# step1710051029.net
KiCad netlist of a schematic drawn in Altium Designer
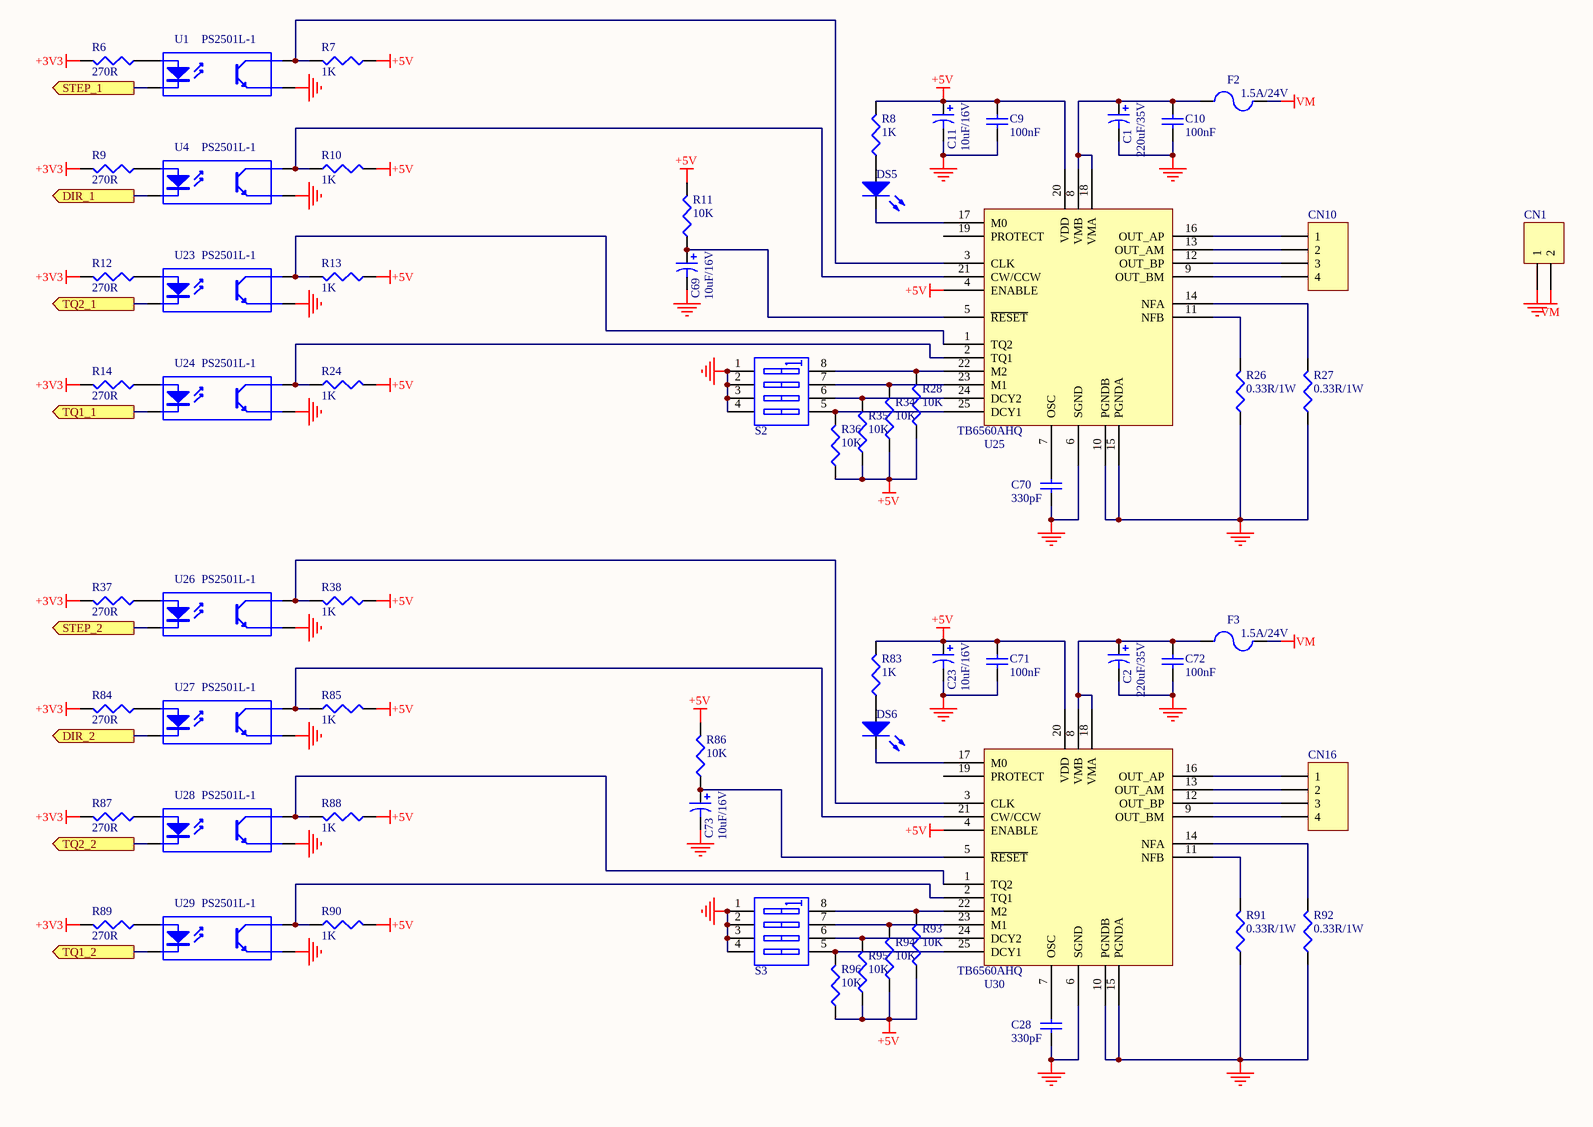
[diagram p0: step1710051029.SchDoc]

(export (version "E")
  (design (tool "Eeschema 10.0.6"))
  (components
    (comp (ref "C1")
      (value "220uF/35V")
      (footprint "CAP-D10/L13")
      (description "Polarized Capacitor (Radial)")
      (fields (field (name "PUBLISHER") "Altium Limited"))
      (libsource (lib "Miscellaneous Devices") (part "Cap Pol1"))
    )
    (comp (ref "C2")
      (value "220uF/35V")
      (footprint "CAP-D10/L13")
      (description "Polarized Capacitor (Radial)")
      (fields (field (name "PUBLISHER") "Altium Limited"))
      (libsource (lib "Miscellaneous Devices") (part "Cap Pol1"))
    )
    (comp (ref "C9")
      (value "100nF")
      (footprint "C0603-3")
      (description "Capacitor")
      (fields (field (name "PUBLISHER") "Altium Limited"))
      (libsource (lib "Miscellaneous Devices") (part "Cap"))
    )
    (comp (ref "C10")
      (value "100nF")
      (footprint "C0603-3")
      (description "Capacitor")
      (fields (field (name "PUBLISHER") "Altium Limited"))
      (libsource (lib "Miscellaneous Devices") (part "Cap"))
    )
    (comp (ref "C11")
      (value "10uF/16V")
      (footprint "CE1210")
      (description "Polarized Capacitor (Radial)")
      (fields (field (name "PUBLISHER") "Altium Limited"))
      (libsource (lib "Miscellaneous Devices") (part "Cap Pol1"))
    )
    (comp (ref "C23")
      (value "10uF/16V")
      (footprint "CE1210")
      (description "Polarized Capacitor (Radial)")
      (fields (field (name "PUBLISHER") "Altium Limited"))
      (libsource (lib "Miscellaneous Devices") (part "Cap Pol1"))
    )
    (comp (ref "C28")
      (value "330pF")
      (footprint "C0603-3")
      (description "Capacitor")
      (fields (field (name "PUBLISHER") "Altium Limited"))
      (libsource (lib "Miscellaneous Devices") (part "Cap"))
    )
    (comp (ref "C69")
      (value "10uF/16V")
      (footprint "CE1210")
      (description "Polarized Capacitor (Radial)")
      (fields (field (name "PUBLISHER") "Altium Limited"))
      (libsource (lib "Miscellaneous Devices") (part "Cap Pol1"))
    )
    (comp (ref "C70")
      (value "330pF")
      (footprint "C0603-3")
      (description "Capacitor")
      (fields (field (name "PUBLISHER") "Altium Limited"))
      (libsource (lib "Miscellaneous Devices") (part "Cap"))
    )
    (comp (ref "C71")
      (value "100nF")
      (footprint "C0603-3")
      (description "Capacitor")
      (fields (field (name "PUBLISHER") "Altium Limited"))
      (libsource (lib "Miscellaneous Devices") (part "Cap"))
    )
    (comp (ref "C72")
      (value "100nF")
      (footprint "C0603-3")
      (description "Capacitor")
      (fields (field (name "PUBLISHER") "Altium Limited"))
      (libsource (lib "Miscellaneous Devices") (part "Cap"))
    )
    (comp (ref "C73")
      (value "10uF/16V")
      (footprint "CE1210")
      (description "Polarized Capacitor (Radial)")
      (fields (field (name "PUBLISHER") "Altium Limited"))
      (libsource (lib "Miscellaneous Devices") (part "Cap Pol1"))
    )
    (comp (ref "CN1")
      (value "~")
      (footprint "XHS2-2.5")
      (description "Header, 2-Pin")
      (fields (field (name "PUBLISHER") "Altium Limited"))
      (libsource (lib "Miscellaneous Connectors") (part "Header 2"))
    )
    (comp (ref "CN10")
      (value "~")
      (footprint "XHS4-2.5")
      (description "Header, 4-Pin")
      (fields (field (name "PUBLISHER") "Altium Limited"))
      (libsource (lib "Miscellaneous Connectors") (part "Header 4"))
    )
    (comp (ref "CN16")
      (value "~")
      (footprint "XHS4-2.5")
      (description "Header, 4-Pin")
      (fields (field (name "PUBLISHER") "Altium Limited"))
      (libsource (lib "Miscellaneous Connectors") (part "Header 4"))
    )
    (comp (ref "DS5")
      (value "~")
      (footprint "LED-0805")
      (description "Typical INFRARED GaAs LED")
      (fields (field (name "PUBLISHER") "Altium Limited"))
      (libsource (lib "Sch1609122025") (part "LED0"))
    )
    (comp (ref "DS6")
      (value "~")
      (footprint "LED-0805")
      (description "Typical INFRARED GaAs LED")
      (fields (field (name "PUBLISHER") "Altium Limited"))
      (libsource (lib "Sch1609122025") (part "LED0"))
    )
    (comp (ref "F2")
      (value "1.5A/24V")
      (footprint "1812")
      (libsource (lib "SchLib1512020919") (part "Fuse 2"))
    )
    (comp (ref "F3")
      (value "1.5A/24V")
      (footprint "1812")
      (libsource (lib "SchLib1512020919") (part "Fuse 2"))
    )
    (comp (ref "R6")
      (value "270R")
      (footprint "R0603-3")
      (description "Resistor")
      (fields (field (name "PUBLISHER") "Altium Limited"))
      (libsource (lib "Miscellaneous Devices") (part "Res3"))
    )
    (comp (ref "R7")
      (value "1K")
      (footprint "R0603-3")
      (description "Resistor")
      (fields (field (name "PUBLISHER") "Altium Limited"))
      (libsource (lib "Miscellaneous Devices") (part "Res3"))
    )
    (comp (ref "R8")
      (value "1K")
      (footprint "R0603-3")
      (description "Resistor")
      (fields (field (name "PUBLISHER") "Altium Limited"))
      (libsource (lib "Miscellaneous Devices") (part "Res3"))
    )
    (comp (ref "R9")
      (value "270R")
      (footprint "R0603-3")
      (description "Resistor")
      (fields (field (name "PUBLISHER") "Altium Limited"))
      (libsource (lib "Miscellaneous Devices") (part "Res3"))
    )
    (comp (ref "R10")
      (value "1K")
      (footprint "R0603-3")
      (description "Resistor")
      (fields (field (name "PUBLISHER") "Altium Limited"))
      (libsource (lib "Miscellaneous Devices") (part "Res3"))
    )
    (comp (ref "R11")
      (value "10K")
      (footprint "R0603-3")
      (description "Resistor")
      (fields (field (name "PUBLISHER") "Altium Limited"))
      (libsource (lib "Miscellaneous Devices") (part "Res3"))
    )
    (comp (ref "R12")
      (value "270R")
      (footprint "R0603-3")
      (description "Resistor")
      (fields (field (name "PUBLISHER") "Altium Limited"))
      (libsource (lib "Miscellaneous Devices") (part "Res3"))
    )
    (comp (ref "R13")
      (value "1K")
      (footprint "R0603-3")
      (description "Resistor")
      (fields (field (name "PUBLISHER") "Altium Limited"))
      (libsource (lib "Miscellaneous Devices") (part "Res3"))
    )
    (comp (ref "R14")
      (value "270R")
      (footprint "R0603-3")
      (description "Resistor")
      (fields (field (name "PUBLISHER") "Altium Limited"))
      (libsource (lib "Miscellaneous Devices") (part "Res3"))
    )
    (comp (ref "R24")
      (value "1K")
      (footprint "R0603-3")
      (description "Resistor")
      (fields (field (name "PUBLISHER") "Altium Limited"))
      (libsource (lib "Miscellaneous Devices") (part "Res3"))
    )
    (comp (ref "R26")
      (value "0.33R/1W")
      (footprint "2512")
      (description "Resistor")
      (fields (field (name "PUBLISHER") "Altium Limited"))
      (libsource (lib "Miscellaneous Devices") (part "Res3"))
    )
    (comp (ref "R27")
      (value "0.33R/1W")
      (footprint "2512")
      (description "Resistor")
      (fields (field (name "PUBLISHER") "Altium Limited"))
      (libsource (lib "Miscellaneous Devices") (part "Res3"))
    )
    (comp (ref "R28")
      (value "10K")
      (footprint "R0603-3")
      (description "Resistor")
      (fields (field (name "PUBLISHER") "Altium Limited"))
      (libsource (lib "Miscellaneous Devices") (part "Res3"))
    )
    (comp (ref "R34")
      (value "10K")
      (footprint "R0603-3")
      (description "Resistor")
      (fields (field (name "PUBLISHER") "Altium Limited"))
      (libsource (lib "Miscellaneous Devices") (part "Res3"))
    )
    (comp (ref "R35")
      (value "10K")
      (footprint "R0603-3")
      (description "Resistor")
      (fields (field (name "PUBLISHER") "Altium Limited"))
      (libsource (lib "Miscellaneous Devices") (part "Res3"))
    )
    (comp (ref "R36")
      (value "10K")
      (footprint "R0603-3")
      (description "Resistor")
      (fields (field (name "PUBLISHER") "Altium Limited"))
      (libsource (lib "Miscellaneous Devices") (part "Res3"))
    )
    (comp (ref "R37")
      (value "270R")
      (footprint "R0603-3")
      (description "Resistor")
      (fields (field (name "PUBLISHER") "Altium Limited"))
      (libsource (lib "Miscellaneous Devices") (part "Res3"))
    )
    (comp (ref "R38")
      (value "1K")
      (footprint "R0603-3")
      (description "Resistor")
      (fields (field (name "PUBLISHER") "Altium Limited"))
      (libsource (lib "Miscellaneous Devices") (part "Res3"))
    )
    (comp (ref "R83")
      (value "1K")
      (footprint "R0603-3")
      (description "Resistor")
      (fields (field (name "PUBLISHER") "Altium Limited"))
      (libsource (lib "Miscellaneous Devices") (part "Res3"))
    )
    (comp (ref "R84")
      (value "270R")
      (footprint "R0603-3")
      (description "Resistor")
      (fields (field (name "PUBLISHER") "Altium Limited"))
      (libsource (lib "Miscellaneous Devices") (part "Res3"))
    )
    (comp (ref "R85")
      (value "1K")
      (footprint "R0603-3")
      (description "Resistor")
      (fields (field (name "PUBLISHER") "Altium Limited"))
      (libsource (lib "Miscellaneous Devices") (part "Res3"))
    )
    (comp (ref "R86")
      (value "10K")
      (footprint "R0603-3")
      (description "Resistor")
      (fields (field (name "PUBLISHER") "Altium Limited"))
      (libsource (lib "Miscellaneous Devices") (part "Res3"))
    )
    (comp (ref "R87")
      (value "270R")
      (footprint "R0603-3")
      (description "Resistor")
      (fields (field (name "PUBLISHER") "Altium Limited"))
      (libsource (lib "Miscellaneous Devices") (part "Res3"))
    )
    (comp (ref "R88")
      (value "1K")
      (footprint "R0603-3")
      (description "Resistor")
      (fields (field (name "PUBLISHER") "Altium Limited"))
      (libsource (lib "Miscellaneous Devices") (part "Res3"))
    )
    (comp (ref "R89")
      (value "270R")
      (footprint "R0603-3")
      (description "Resistor")
      (fields (field (name "PUBLISHER") "Altium Limited"))
      (libsource (lib "Miscellaneous Devices") (part "Res3"))
    )
    (comp (ref "R90")
      (value "1K")
      (footprint "R0603-3")
      (description "Resistor")
      (fields (field (name "PUBLISHER") "Altium Limited"))
      (libsource (lib "Miscellaneous Devices") (part "Res3"))
    )
    (comp (ref "R91")
      (value "0.33R/1W")
      (footprint "2512")
      (description "Resistor")
      (fields (field (name "PUBLISHER") "Altium Limited"))
      (libsource (lib "Miscellaneous Devices") (part "Res3"))
    )
    (comp (ref "R92")
      (value "0.33R/1W")
      (footprint "2512")
      (description "Resistor")
      (fields (field (name "PUBLISHER") "Altium Limited"))
      (libsource (lib "Miscellaneous Devices") (part "Res3"))
    )
    (comp (ref "R93")
      (value "10K")
      (footprint "R0603-3")
      (description "Resistor")
      (fields (field (name "PUBLISHER") "Altium Limited"))
      (libsource (lib "Miscellaneous Devices") (part "Res3"))
    )
    (comp (ref "R94")
      (value "10K")
      (footprint "R0603-3")
      (description "Resistor")
      (fields (field (name "PUBLISHER") "Altium Limited"))
      (libsource (lib "Miscellaneous Devices") (part "Res3"))
    )
    (comp (ref "R95")
      (value "10K")
      (footprint "R0603-3")
      (description "Resistor")
      (fields (field (name "PUBLISHER") "Altium Limited"))
      (libsource (lib "Miscellaneous Devices") (part "Res3"))
    )
    (comp (ref "R96")
      (value "10K")
      (footprint "R0603-3")
      (description "Resistor")
      (fields (field (name "PUBLISHER") "Altium Limited"))
      (libsource (lib "Miscellaneous Devices") (part "Res3"))
    )
    (comp (ref "S2")
      (value "~")
      (footprint "SDSW8-H")
      (description "DIP Switch, 4 Position, SPST")
      (fields (field (name "PUBLISHER") "Altium Limited"))
      (libsource (lib "Miscellaneous Devices") (part "SW DIP-4"))
    )
    (comp (ref "S3")
      (value "~")
      (footprint "SDSW8-H")
      (description "DIP Switch, 4 Position, SPST")
      (fields (field (name "PUBLISHER") "Altium Limited"))
      (libsource (lib "Miscellaneous Devices") (part "SW DIP-4"))
    )
    (comp (ref "U1")
      (value "PS2501L-1")
      (footprint "SOP4-2.54")
      (libsource (lib "GprsCanSchLib") (part "PC187"))
    )
    (comp (ref "U4")
      (value "PS2501L-1")
      (footprint "SOP4-2.54")
      (libsource (lib "GprsCanSchLib") (part "PC187"))
    )
    (comp (ref "U23")
      (value "PS2501L-1")
      (footprint "SOP4-2.54")
      (libsource (lib "GprsCanSchLib") (part "PC187"))
    )
    (comp (ref "U24")
      (value "PS2501L-1")
      (footprint "SOP4-2.54")
      (libsource (lib "GprsCanSchLib") (part "PC187"))
    )
    (comp (ref "U25")
      (value "TB6560AHQ")
      (footprint "HZIP25-P-1.27")
      (description "PWM Chopper-Type Bipolar Driver IC for Stepping Motor Control")
      (libsource (lib "Sch1705290855") (part "TB6560AHQ"))
    )
    (comp (ref "U26")
      (value "PS2501L-1")
      (footprint "SOP4-2.54")
      (libsource (lib "GprsCanSchLib") (part "PC187"))
    )
    (comp (ref "U27")
      (value "PS2501L-1")
      (footprint "SOP4-2.54")
      (libsource (lib "GprsCanSchLib") (part "PC187"))
    )
    (comp (ref "U28")
      (value "PS2501L-1")
      (footprint "SOP4-2.54")
      (libsource (lib "GprsCanSchLib") (part "PC187"))
    )
    (comp (ref "U29")
      (value "PS2501L-1")
      (footprint "SOP4-2.54")
      (libsource (lib "GprsCanSchLib") (part "PC187"))
    )
    (comp (ref "U30")
      (value "TB6560AHQ")
      (footprint "HZIP25-P-1.27")
      (description "PWM Chopper-Type Bipolar Driver IC for Stepping Motor Control")
      (libsource (lib "Sch1705290855") (part "TB6560AHQ"))
    )
  )
  (nets
    (net (code "1") (name "+3V3") (class "Default")
      (node (ref "R12") (pin "2") (pinfunction "2_2") (pintype "passive"))
      (node (ref "R14") (pin "2") (pinfunction "2_2") (pintype "passive"))
      (node (ref "R37") (pin "2") (pinfunction "2_2") (pintype "passive"))
      (node (ref "R6") (pin "2") (pinfunction "2_2") (pintype "passive"))
      (node (ref "R84") (pin "2") (pinfunction "2_2") (pintype "passive"))
      (node (ref "R87") (pin "2") (pinfunction "2_2") (pintype "passive"))
      (node (ref "R89") (pin "2") (pinfunction "2_2") (pintype "passive"))
      (node (ref "R9") (pin "2") (pinfunction "2_2") (pintype "passive"))
    )
    (net (code "2") (name "+5V") (class "Default")
      (node (ref "C11") (pin "1") (pinfunction "1_1") (pintype "passive"))
      (node (ref "C23") (pin "1") (pinfunction "1_1") (pintype "passive"))
      (node (ref "C71") (pin "1") (pinfunction "1_1") (pintype "passive"))
      (node (ref "C9") (pin "1") (pinfunction "1_1") (pintype "passive"))
      (node (ref "R10") (pin "2") (pinfunction "2_2") (pintype "passive"))
      (node (ref "R11") (pin "2") (pinfunction "2_2") (pintype "passive"))
      (node (ref "R13") (pin "1") (pinfunction "1_1") (pintype "passive"))
      (node (ref "R24") (pin "2") (pinfunction "2_2") (pintype "passive"))
      (node (ref "R28") (pin "1") (pinfunction "1_1") (pintype "passive"))
      (node (ref "R34") (pin "1") (pinfunction "1_1") (pintype "passive"))
      (node (ref "R35") (pin "1") (pinfunction "1_1") (pintype "passive"))
      (node (ref "R36") (pin "1") (pinfunction "1_1") (pintype "passive"))
      (node (ref "R38") (pin "1") (pinfunction "1_1") (pintype "passive"))
      (node (ref "R7") (pin "1") (pinfunction "1_1") (pintype "passive"))
      (node (ref "R8") (pin "2") (pinfunction "2_2") (pintype "passive"))
      (node (ref "R83") (pin "2") (pinfunction "2_2") (pintype "passive"))
      (node (ref "R85") (pin "2") (pinfunction "2_2") (pintype "passive"))
      (node (ref "R86") (pin "2") (pinfunction "2_2") (pintype "passive"))
      (node (ref "R88") (pin "1") (pinfunction "1_1") (pintype "passive"))
      (node (ref "R90") (pin "2") (pinfunction "2_2") (pintype "passive"))
      (node (ref "R93") (pin "1") (pinfunction "1_1") (pintype "passive"))
      (node (ref "R94") (pin "1") (pinfunction "1_1") (pintype "passive"))
      (node (ref "R95") (pin "1") (pinfunction "1_1") (pintype "passive"))
      (node (ref "R96") (pin "1") (pinfunction "1_1") (pintype "passive"))
      (node (ref "U25") (pin "20") (pinfunction "VDD_20") (pintype "passive"))
      (node (ref "U25") (pin "4") (pinfunction "ENABLE_4") (pintype "passive"))
      (node (ref "U30") (pin "20") (pinfunction "VDD_20") (pintype "passive"))
      (node (ref "U30") (pin "4") (pinfunction "ENABLE_4") (pintype "passive"))
    )
    (net (code "3") (name "/DIR_1") (class "Default")
      (node (ref "U4") (pin "2") (pinfunction "K_2") (pintype "passive"))
    )
    (net (code "4") (name "/DIR_2") (class "Default")
      (node (ref "U27") (pin "2") (pinfunction "K_2") (pintype "passive"))
    )
    (net (code "5") (name "/STEP_1") (class "Default")
      (node (ref "U1") (pin "2") (pinfunction "K_2") (pintype "passive"))
    )
    (net (code "6") (name "/STEP_2") (class "Default")
      (node (ref "U26") (pin "2") (pinfunction "K_2") (pintype "passive"))
    )
    (net (code "7") (name "/TQ1_1") (class "Default")
      (node (ref "U24") (pin "2") (pinfunction "K_2") (pintype "passive"))
    )
    (net (code "8") (name "/TQ1_2") (class "Default")
      (node (ref "U29") (pin "2") (pinfunction "K_2") (pintype "passive"))
    )
    (net (code "9") (name "/TQ2_1") (class "Default")
      (node (ref "U23") (pin "2") (pinfunction "K_2") (pintype "passive"))
    )
    (net (code "10") (name "/TQ2_2") (class "Default")
      (node (ref "U28") (pin "2") (pinfunction "K_2") (pintype "passive"))
    )
    (net (code "11") (name "GND") (class "Default")
      (node (ref "C1") (pin "2") (pinfunction "2_2") (pintype "passive"))
      (node (ref "C10") (pin "2") (pinfunction "2_2") (pintype "passive"))
      (node (ref "C11") (pin "2") (pinfunction "2_2") (pintype "passive"))
      (node (ref "C2") (pin "2") (pinfunction "2_2") (pintype "passive"))
      (node (ref "C23") (pin "2") (pinfunction "2_2") (pintype "passive"))
      (node (ref "C28") (pin "2") (pinfunction "2_2") (pintype "passive"))
      (node (ref "C69") (pin "2") (pinfunction "2_2") (pintype "passive"))
      (node (ref "C70") (pin "2") (pinfunction "2_2") (pintype "passive"))
      (node (ref "C71") (pin "2") (pinfunction "2_2") (pintype "passive"))
      (node (ref "C72") (pin "2") (pinfunction "2_2") (pintype "passive"))
      (node (ref "C73") (pin "2") (pinfunction "2_2") (pintype "passive"))
      (node (ref "C9") (pin "2") (pinfunction "2_2") (pintype "passive"))
      (node (ref "CN1") (pin "1") (pinfunction "1_1") (pintype "passive"))
      (node (ref "R26") (pin "1") (pinfunction "1_1") (pintype "passive"))
      (node (ref "R27") (pin "1") (pinfunction "1_1") (pintype "passive"))
      (node (ref "R91") (pin "1") (pinfunction "1_1") (pintype "passive"))
      (node (ref "R92") (pin "1") (pinfunction "1_1") (pintype "passive"))
      (node (ref "S2") (pin "1") (pinfunction "A1_1") (pintype "passive"))
      (node (ref "S2") (pin "2") (pinfunction "A2_2") (pintype "passive"))
      (node (ref "S2") (pin "3") (pinfunction "A3_3") (pintype "passive"))
      (node (ref "S2") (pin "4") (pinfunction "A4_4") (pintype "passive"))
      (node (ref "S3") (pin "1") (pinfunction "A1_1") (pintype "passive"))
      (node (ref "S3") (pin "2") (pinfunction "A2_2") (pintype "passive"))
      (node (ref "S3") (pin "3") (pinfunction "A3_3") (pintype "passive"))
      (node (ref "S3") (pin "4") (pinfunction "A4_4") (pintype "passive"))
      (node (ref "U1") (pin "3") (pinfunction "C_3") (pintype "passive"))
      (node (ref "U23") (pin "3") (pinfunction "C_3") (pintype "passive"))
      (node (ref "U24") (pin "3") (pinfunction "C_3") (pintype "passive"))
      (node (ref "U25") (pin "10") (pinfunction "PGNDB_10") (pintype "passive"))
      (node (ref "U25") (pin "15") (pinfunction "PGNDA_15") (pintype "passive"))
      (node (ref "U25") (pin "6") (pinfunction "SGND_6") (pintype "passive"))
      (node (ref "U26") (pin "3") (pinfunction "C_3") (pintype "passive"))
      (node (ref "U27") (pin "3") (pinfunction "C_3") (pintype "passive"))
      (node (ref "U28") (pin "3") (pinfunction "C_3") (pintype "passive"))
      (node (ref "U29") (pin "3") (pinfunction "C_3") (pintype "passive"))
      (node (ref "U30") (pin "10") (pinfunction "PGNDB_10") (pintype "passive"))
      (node (ref "U30") (pin "15") (pinfunction "PGNDA_15") (pintype "passive"))
      (node (ref "U30") (pin "6") (pinfunction "SGND_6") (pintype "passive"))
      (node (ref "U4") (pin "3") (pinfunction "C_3") (pintype "passive"))
    )
    (net (code "12") (name "Net-(DS5-A)") (class "Default")
      (node (ref "DS5") (pin "1") (pinfunction "A_1") (pintype "passive"))
      (node (ref "R8") (pin "1") (pinfunction "1_1") (pintype "passive"))
    )
    (net (code "13") (name "Net-(DS5-K)") (class "Default")
      (node (ref "DS5") (pin "2") (pinfunction "K_2") (pintype "passive"))
      (node (ref "U25") (pin "17") (pinfunction "M0_17") (pintype "passive"))
    )
    (net (code "14") (name "Net-(DS6-A)") (class "Default")
      (node (ref "DS6") (pin "1") (pinfunction "A_1") (pintype "passive"))
      (node (ref "R83") (pin "1") (pinfunction "1_1") (pintype "passive"))
    )
    (net (code "15") (name "Net-(DS6-K)") (class "Default")
      (node (ref "DS6") (pin "2") (pinfunction "K_2") (pintype "passive"))
      (node (ref "U30") (pin "17") (pinfunction "M0_17") (pintype "passive"))
    )
    (net (code "16") (name "Net-(S2-B1)") (class "Default")
      (node (ref "R28") (pin "2") (pinfunction "2_2") (pintype "passive"))
      (node (ref "S2") (pin "8") (pinfunction "B1_8") (pintype "passive"))
      (node (ref "U25") (pin "22") (pinfunction "M2_22") (pintype "passive"))
    )
    (net (code "17") (name "Net-(S2-B2)") (class "Default")
      (node (ref "R34") (pin "2") (pinfunction "2_2") (pintype "passive"))
      (node (ref "S2") (pin "7") (pinfunction "B2_7") (pintype "passive"))
      (node (ref "U25") (pin "23") (pinfunction "M1_23") (pintype "passive"))
    )
    (net (code "18") (name "Net-(S2-B3)") (class "Default")
      (node (ref "R35") (pin "2") (pinfunction "2_2") (pintype "passive"))
      (node (ref "S2") (pin "6") (pinfunction "B3_6") (pintype "passive"))
      (node (ref "U25") (pin "24") (pinfunction "DCY2_24") (pintype "passive"))
    )
    (net (code "19") (name "Net-(S2-B4)") (class "Default")
      (node (ref "R36") (pin "2") (pinfunction "2_2") (pintype "passive"))
      (node (ref "S2") (pin "5") (pinfunction "B4_5") (pintype "passive"))
      (node (ref "U25") (pin "25") (pinfunction "DCY1_25") (pintype "passive"))
    )
    (net (code "20") (name "Net-(S3-B1)") (class "Default")
      (node (ref "R93") (pin "2") (pinfunction "2_2") (pintype "passive"))
      (node (ref "S3") (pin "8") (pinfunction "B1_8") (pintype "passive"))
      (node (ref "U30") (pin "22") (pinfunction "M2_22") (pintype "passive"))
    )
    (net (code "21") (name "Net-(S3-B2)") (class "Default")
      (node (ref "R94") (pin "2") (pinfunction "2_2") (pintype "passive"))
      (node (ref "S3") (pin "7") (pinfunction "B2_7") (pintype "passive"))
      (node (ref "U30") (pin "23") (pinfunction "M1_23") (pintype "passive"))
    )
    (net (code "22") (name "Net-(S3-B3)") (class "Default")
      (node (ref "R95") (pin "2") (pinfunction "2_2") (pintype "passive"))
      (node (ref "S3") (pin "6") (pinfunction "B3_6") (pintype "passive"))
      (node (ref "U30") (pin "24") (pinfunction "DCY2_24") (pintype "passive"))
    )
    (net (code "23") (name "Net-(S3-B4)") (class "Default")
      (node (ref "R96") (pin "2") (pinfunction "2_2") (pintype "passive"))
      (node (ref "S3") (pin "5") (pinfunction "B4_5") (pintype "passive"))
      (node (ref "U30") (pin "25") (pinfunction "DCY1_25") (pintype "passive"))
    )
    (net (code "24") (name "Net-(U1-A)") (class "Default")
      (node (ref "R6") (pin "1") (pinfunction "1_1") (pintype "passive"))
      (node (ref "U1") (pin "1") (pinfunction "A_1") (pintype "passive"))
    )
    (net (code "25") (name "Net-(U1-D)") (class "Default")
      (node (ref "R7") (pin "2") (pinfunction "2_2") (pintype "passive"))
      (node (ref "U1") (pin "4") (pinfunction "D_4") (pintype "passive"))
      (node (ref "U25") (pin "3") (pinfunction "CLK_3") (pintype "passive"))
    )
    (net (code "26") (name "Net-(U4-A)") (class "Default")
      (node (ref "R9") (pin "1") (pinfunction "1_1") (pintype "passive"))
      (node (ref "U4") (pin "1") (pinfunction "A_1") (pintype "passive"))
    )
    (net (code "27") (name "Net-(U23-A)") (class "Default")
      (node (ref "R12") (pin "1") (pinfunction "1_1") (pintype "passive"))
      (node (ref "U23") (pin "1") (pinfunction "A_1") (pintype "passive"))
    )
    (net (code "28") (name "Net-(U23-D)") (class "Default")
      (node (ref "R13") (pin "2") (pinfunction "2_2") (pintype "passive"))
      (node (ref "U23") (pin "4") (pinfunction "D_4") (pintype "passive"))
      (node (ref "U25") (pin "1") (pinfunction "TQ2_1") (pintype "passive"))
    )
    (net (code "29") (name "Net-(U24-A)") (class "Default")
      (node (ref "R14") (pin "1") (pinfunction "1_1") (pintype "passive"))
      (node (ref "U24") (pin "1") (pinfunction "A_1") (pintype "passive"))
    )
    (net (code "30") (name "Net-(U24-D)") (class "Default")
      (node (ref "R24") (pin "1") (pinfunction "1_1") (pintype "passive"))
      (node (ref "U24") (pin "4") (pinfunction "D_4") (pintype "passive"))
      (node (ref "U25") (pin "2") (pinfunction "TQ1_2") (pintype "passive"))
    )
    (net (code "31") (name "Net-(U25-CW{slash}CCW)") (class "Default")
      (node (ref "R10") (pin "1") (pinfunction "1_1") (pintype "passive"))
      (node (ref "U25") (pin "21") (pinfunction "CW/CCW_21") (pintype "passive"))
      (node (ref "U4") (pin "4") (pinfunction "D_4") (pintype "passive"))
    )
    (net (code "32") (name "Net-(U25-NFA)") (class "Default")
      (node (ref "R27") (pin "2") (pinfunction "2_2") (pintype "passive"))
      (node (ref "U25") (pin "14") (pinfunction "NFA_14") (pintype "passive"))
    )
    (net (code "33") (name "Net-(U25-NFB)") (class "Default")
      (node (ref "R26") (pin "2") (pinfunction "2_2") (pintype "passive"))
      (node (ref "U25") (pin "11") (pinfunction "NFB_11") (pintype "passive"))
    )
    (net (code "34") (name "Net-(U25-OSC)") (class "Default")
      (node (ref "C70") (pin "1") (pinfunction "1_1") (pintype "passive"))
      (node (ref "U25") (pin "7") (pinfunction "OSC_7") (pintype "passive"))
    )
    (net (code "35") (name "Net-(U25-OUT_AM)") (class "Default")
      (node (ref "CN10") (pin "2") (pinfunction "2_2") (pintype "passive"))
      (node (ref "U25") (pin "13") (pinfunction "OUT_AM_13") (pintype "passive"))
    )
    (net (code "36") (name "Net-(U25-OUT_AP)") (class "Default")
      (node (ref "CN10") (pin "1") (pinfunction "1_1") (pintype "passive"))
      (node (ref "U25") (pin "16") (pinfunction "OUT_AP_16") (pintype "passive"))
    )
    (net (code "37") (name "Net-(U25-OUT_BM)") (class "Default")
      (node (ref "CN10") (pin "4") (pinfunction "4_4") (pintype "passive"))
      (node (ref "U25") (pin "9") (pinfunction "OUT_BM_9") (pintype "passive"))
    )
    (net (code "38") (name "Net-(U25-OUT_BP)") (class "Default")
      (node (ref "CN10") (pin "3") (pinfunction "3_3") (pintype "passive"))
      (node (ref "U25") (pin "12") (pinfunction "OUT_BP_12") (pintype "passive"))
    )
    (net (code "39") (name "Net-(U25-VMA)") (class "Default")
      (node (ref "C1") (pin "1") (pinfunction "1_1") (pintype "passive"))
      (node (ref "C10") (pin "1") (pinfunction "1_1") (pintype "passive"))
      (node (ref "F2") (pin "1") (pinfunction "1_1") (pintype "passive"))
      (node (ref "U25") (pin "18") (pinfunction "VMA_18") (pintype "passive"))
      (node (ref "U25") (pin "8") (pinfunction "VMB_8") (pintype "passive"))
    )
    (net (code "40") (name "Net-(U25-~{RESET})") (class "Default")
      (node (ref "C69") (pin "1") (pinfunction "1_1") (pintype "passive"))
      (node (ref "R11") (pin "1") (pinfunction "1_1") (pintype "passive"))
      (node (ref "U25") (pin "5") (pinfunction "~{RESET}_5") (pintype "passive"))
    )
    (net (code "41") (name "Net-(U26-A)") (class "Default")
      (node (ref "R37") (pin "1") (pinfunction "1_1") (pintype "passive"))
      (node (ref "U26") (pin "1") (pinfunction "A_1") (pintype "passive"))
    )
    (net (code "42") (name "Net-(U26-D)") (class "Default")
      (node (ref "R38") (pin "2") (pinfunction "2_2") (pintype "passive"))
      (node (ref "U26") (pin "4") (pinfunction "D_4") (pintype "passive"))
      (node (ref "U30") (pin "3") (pinfunction "CLK_3") (pintype "passive"))
    )
    (net (code "43") (name "Net-(U27-A)") (class "Default")
      (node (ref "R84") (pin "1") (pinfunction "1_1") (pintype "passive"))
      (node (ref "U27") (pin "1") (pinfunction "A_1") (pintype "passive"))
    )
    (net (code "44") (name "Net-(U27-D)") (class "Default")
      (node (ref "R85") (pin "1") (pinfunction "1_1") (pintype "passive"))
      (node (ref "U27") (pin "4") (pinfunction "D_4") (pintype "passive"))
      (node (ref "U30") (pin "21") (pinfunction "CW/CCW_21") (pintype "passive"))
    )
    (net (code "45") (name "Net-(U28-A)") (class "Default")
      (node (ref "R87") (pin "1") (pinfunction "1_1") (pintype "passive"))
      (node (ref "U28") (pin "1") (pinfunction "A_1") (pintype "passive"))
    )
    (net (code "46") (name "Net-(U28-D)") (class "Default")
      (node (ref "R88") (pin "2") (pinfunction "2_2") (pintype "passive"))
      (node (ref "U28") (pin "4") (pinfunction "D_4") (pintype "passive"))
      (node (ref "U30") (pin "1") (pinfunction "TQ2_1") (pintype "passive"))
    )
    (net (code "47") (name "Net-(U29-A)") (class "Default")
      (node (ref "R89") (pin "1") (pinfunction "1_1") (pintype "passive"))
      (node (ref "U29") (pin "1") (pinfunction "A_1") (pintype "passive"))
    )
    (net (code "48") (name "Net-(U29-D)") (class "Default")
      (node (ref "R90") (pin "1") (pinfunction "1_1") (pintype "passive"))
      (node (ref "U29") (pin "4") (pinfunction "D_4") (pintype "passive"))
      (node (ref "U30") (pin "2") (pinfunction "TQ1_2") (pintype "passive"))
    )
    (net (code "49") (name "Net-(U30-NFA)") (class "Default")
      (node (ref "R92") (pin "2") (pinfunction "2_2") (pintype "passive"))
      (node (ref "U30") (pin "14") (pinfunction "NFA_14") (pintype "passive"))
    )
    (net (code "50") (name "Net-(U30-NFB)") (class "Default")
      (node (ref "R91") (pin "2") (pinfunction "2_2") (pintype "passive"))
      (node (ref "U30") (pin "11") (pinfunction "NFB_11") (pintype "passive"))
    )
    (net (code "51") (name "Net-(U30-OSC)") (class "Default")
      (node (ref "C28") (pin "1") (pinfunction "1_1") (pintype "passive"))
      (node (ref "U30") (pin "7") (pinfunction "OSC_7") (pintype "passive"))
    )
    (net (code "52") (name "Net-(U30-OUT_AM)") (class "Default")
      (node (ref "CN16") (pin "2") (pinfunction "2_2") (pintype "passive"))
      (node (ref "U30") (pin "13") (pinfunction "OUT_AM_13") (pintype "passive"))
    )
    (net (code "53") (name "Net-(U30-OUT_AP)") (class "Default")
      (node (ref "CN16") (pin "1") (pinfunction "1_1") (pintype "passive"))
      (node (ref "U30") (pin "16") (pinfunction "OUT_AP_16") (pintype "passive"))
    )
    (net (code "54") (name "Net-(U30-OUT_BM)") (class "Default")
      (node (ref "CN16") (pin "4") (pinfunction "4_4") (pintype "passive"))
      (node (ref "U30") (pin "9") (pinfunction "OUT_BM_9") (pintype "passive"))
    )
    (net (code "55") (name "Net-(U30-OUT_BP)") (class "Default")
      (node (ref "CN16") (pin "3") (pinfunction "3_3") (pintype "passive"))
      (node (ref "U30") (pin "12") (pinfunction "OUT_BP_12") (pintype "passive"))
    )
    (net (code "56") (name "Net-(U30-VMA)") (class "Default")
      (node (ref "C2") (pin "1") (pinfunction "1_1") (pintype "passive"))
      (node (ref "C72") (pin "1") (pinfunction "1_1") (pintype "passive"))
      (node (ref "F3") (pin "1") (pinfunction "1_1") (pintype "passive"))
      (node (ref "U30") (pin "18") (pinfunction "VMA_18") (pintype "passive"))
      (node (ref "U30") (pin "8") (pinfunction "VMB_8") (pintype "passive"))
    )
    (net (code "57") (name "Net-(U30-~{RESET})") (class "Default")
      (node (ref "C73") (pin "1") (pinfunction "1_1") (pintype "passive"))
      (node (ref "R86") (pin "1") (pinfunction "1_1") (pintype "passive"))
      (node (ref "U30") (pin "5") (pinfunction "~{RESET}_5") (pintype "passive"))
    )
    (net (code "58") (name "VM") (class "Default")
      (node (ref "CN1") (pin "2") (pinfunction "2_2") (pintype "passive"))
      (node (ref "F2") (pin "2") (pinfunction "2_2") (pintype "passive"))
      (node (ref "F3") (pin "2") (pinfunction "2_2") (pintype "passive"))
    )
    (net (code "59") (name "unconnected-(U25-PROTECT-Pad19)") (class "Default")
      (node (ref "U25") (pin "19") (pinfunction "PROTECT_19") (pintype "passive"))
    )
    (net (code "60") (name "unconnected-(U30-PROTECT-Pad19)") (class "Default")
      (node (ref "U30") (pin "19") (pinfunction "PROTECT_19") (pintype "passive"))
    )
  )
)
